# keycontrol1.net
KiCad netlist of a schematic drawn in Altium Designer
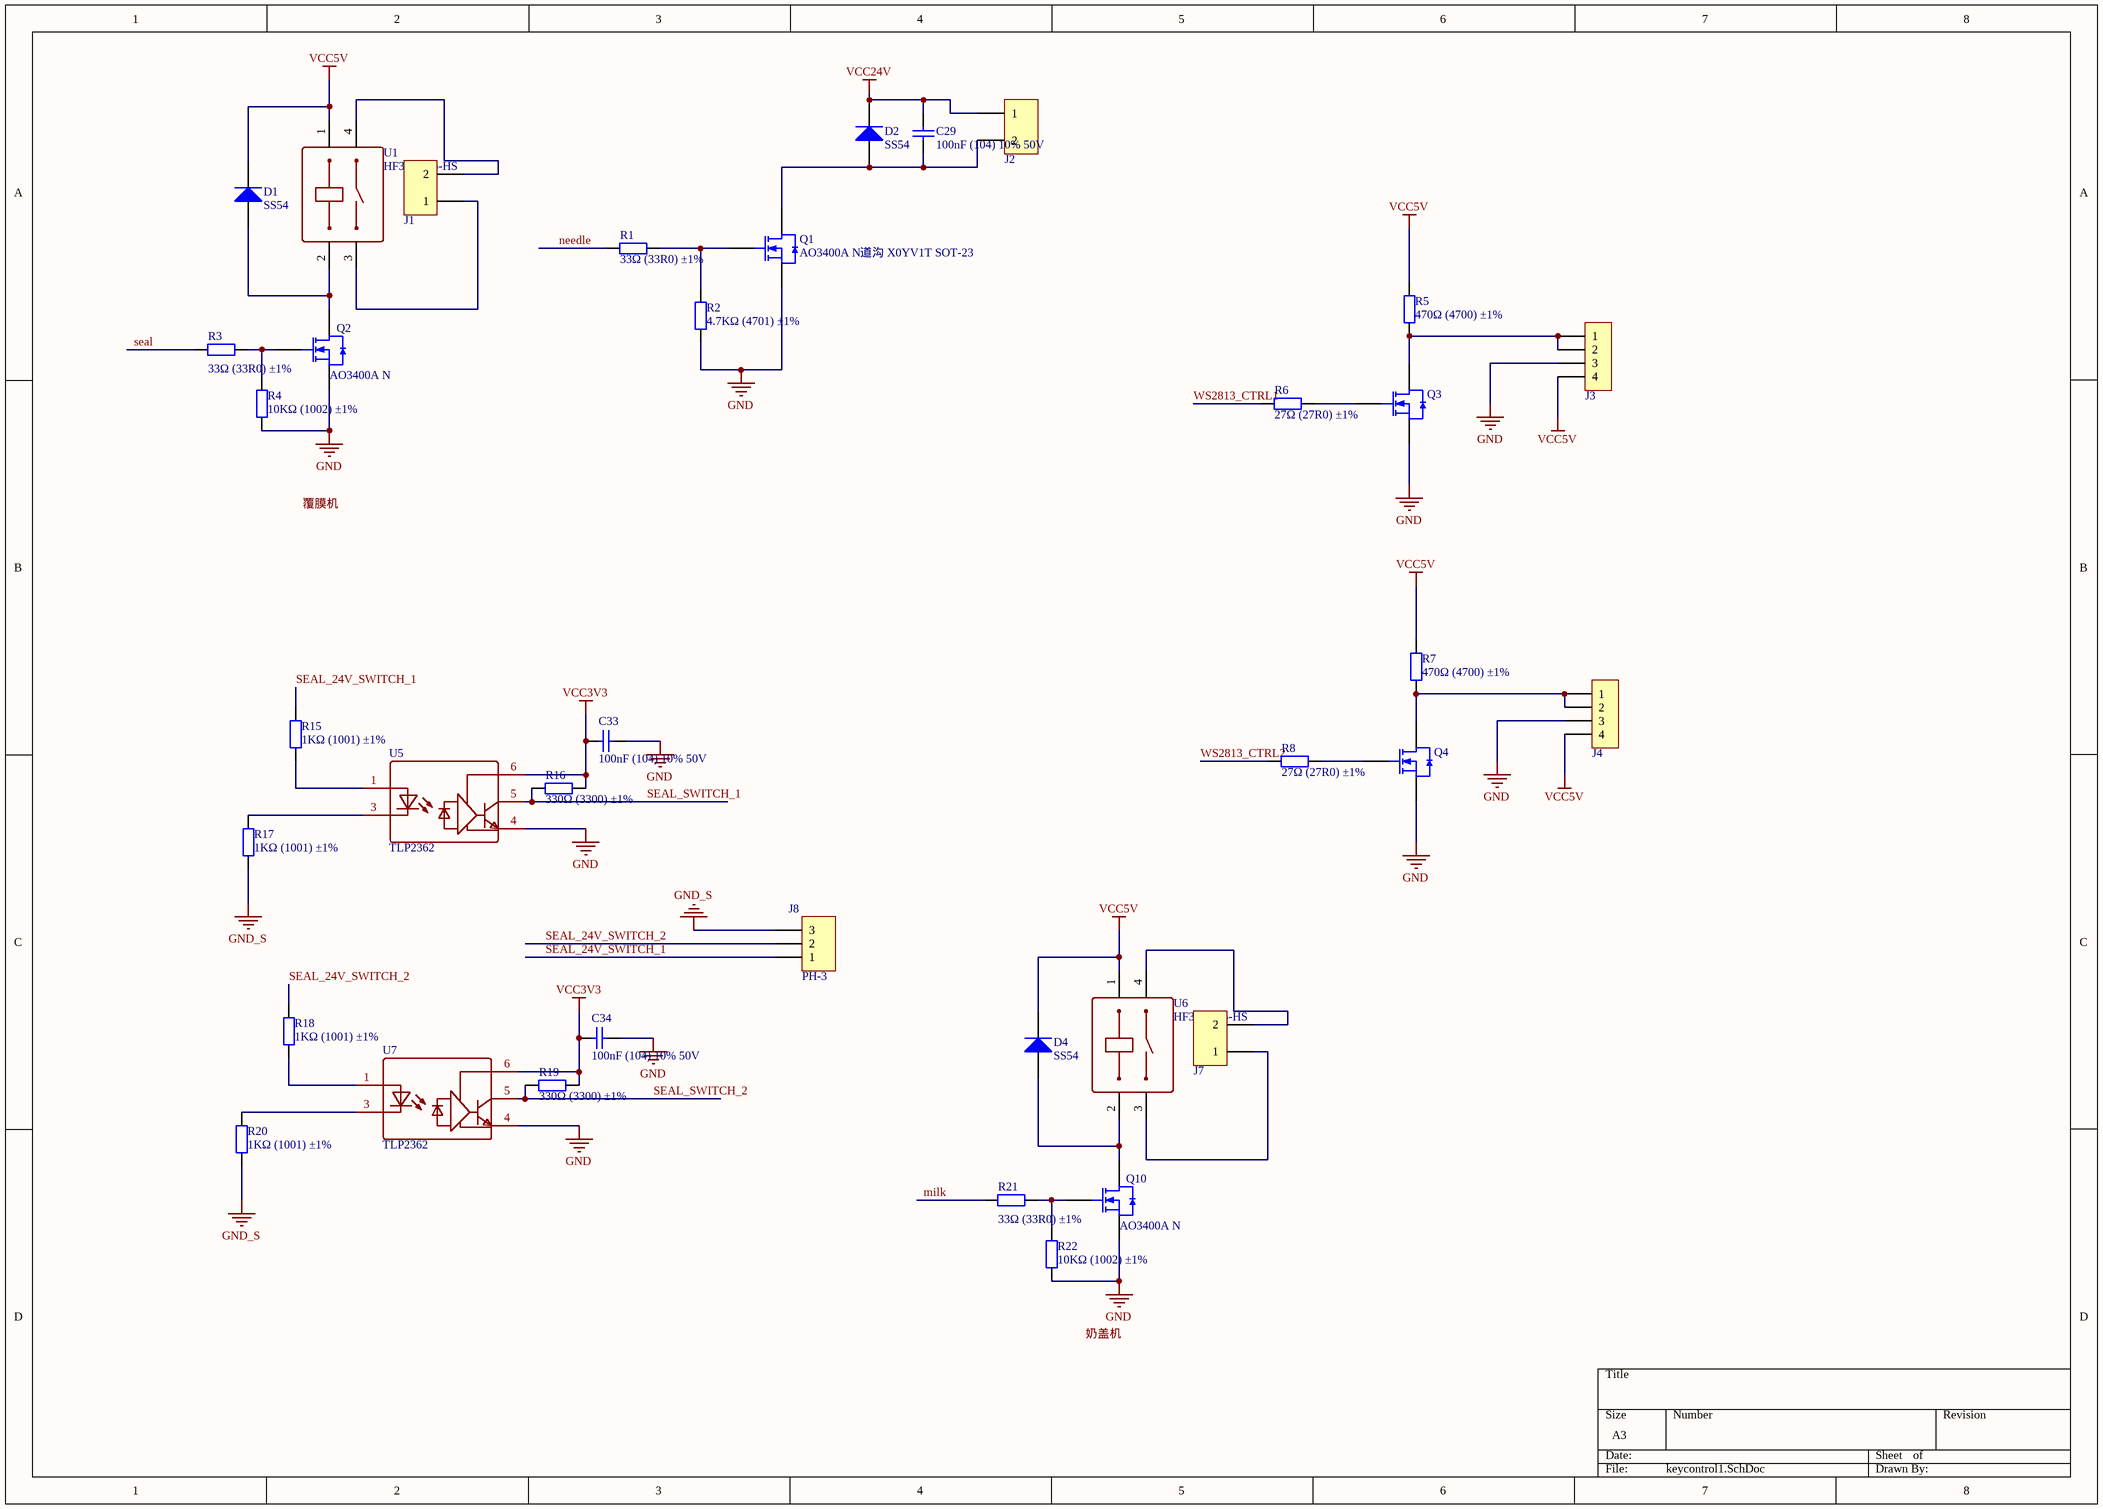
[diagram p0: keycontrol1.SchDoc]

(export (version "E")
  (design (tool "Eeschema 10.0.6"))
  (components
    (comp (ref "C29")
      (value "100nF (104) 10% 50V")
      (footprint "0603_C")
      (description "贴片电容")
      (libsource (lib "AD封装2018.9.19Miscellaneous Devices LC") (part "0603 100nF (104) 10% 50V"))
    )
    (comp (ref "C33")
      (value "100nF (104) 10% 50V")
      (footprint "0603_C")
      (description "贴片电容")
      (libsource (lib "AD封装2018.9.19Miscellaneous Devices LC") (part "0603 100nF (104) 10% 50V"))
    )
    (comp (ref "C34")
      (value "100nF (104) 10% 50V")
      (footprint "0603_C")
      (description "贴片电容")
      (libsource (lib "AD封装2018.9.19Miscellaneous Devices LC") (part "0603 100nF (104) 10% 50V"))
    )
    (comp (ref "D1")
      (value "SS54")
      (footprint "SMA(DO-214AC)_S1")
      (description "二极管")
      (libsource (lib "AD封装2018.9.19Miscellaneous Devices LC") (part "SMA(DO-214AC) SS54"))
    )
    (comp (ref "D2")
      (value "SS54")
      (footprint "SMA(DO-214AC)_S1")
      (description "二极管")
      (libsource (lib "AD封装2018.9.19Miscellaneous Devices LC") (part "SMA(DO-214AC) SS54"))
    )
    (comp (ref "D4")
      (value "SS54")
      (footprint "SMA(DO-214AC)_S1")
      (description "二极管")
      (libsource (lib "AD封装2018.9.19Miscellaneous Devices LC") (part "SMA(DO-214AC) SS54"))
    )
    (comp (ref "J1") (value "MOTOR") (footprint "PH2-2.0") (libsource (lib "我的集成库") (part "header2")))
    (comp (ref "J2") (value "MOTOR") (footprint "XH-2P") (libsource (lib "") (part "header2_1")))
    (comp (ref "J3") (value "header4") (footprint "xh-4") (libsource (lib "我的集成库") (part "header4")))
    (comp (ref "J4") (value "header4") (footprint "xh-4") (libsource (lib "我的集成库") (part "header4")))
    (comp (ref "J7") (value "MOTOR") (footprint "PH2-2.0") (libsource (lib "我的集成库") (part "header2")))
    (comp (ref "J8") (value "PH-3") (footprint "ph3-2.0") (libsource (lib "我的集成库") (part "XH-3")))
    (comp (ref "Q1")
      (value "AO3400A N道沟 X0YV1T SOT-23")
      (footprint "SOT-23-3L")
      (description "MOS(场效应管)")
      (libsource (lib "AD封装2018.9.19Miscellaneous Devices LC") (part "AO3400A N道沟 X0YV1T SOT-23"))
    )
    (comp (ref "Q2")
      (value "AO3400A N")
      (footprint "SOT-23-3L")
      (description "MOS(场效应管)")
      (libsource (lib "AD封装2018.9.19Miscellaneous Devices LC") (part "AO3400A N道沟 X0YV1T SOT-23"))
    )
    (comp (ref "Q3")
      (value "AO3400A N道沟 X0YV1T SOT-23")
      (footprint "SOT-23-3L")
      (description "MOS(场效应管)")
      (libsource (lib "AD封装2018.9.19Miscellaneous Devices LC") (part "AO3400A N道沟 X0YV1T SOT-23"))
    )
    (comp (ref "Q4")
      (value "AO3400A N道沟 X0YV1T SOT-23")
      (footprint "SOT-23-3L")
      (description "MOS(场效应管)")
      (libsource (lib "AD封装2018.9.19Miscellaneous Devices LC") (part "AO3400A N道沟 X0YV1T SOT-23"))
    )
    (comp (ref "Q10")
      (value "AO3400A N")
      (footprint "SOT-23-3L")
      (description "MOS(场效应管)")
      (libsource (lib "AD封装2018.9.19Miscellaneous Devices LC") (part "AO3400A N道沟 X0YV1T SOT-23"))
    )
    (comp (ref "R1")
      (value "33Ω (33R0) ±1%")
      (footprint "0603_R")
      (description "贴片电阻")
      (libsource (lib "AD封装2018.9.19Miscellaneous Devices LC") (part "0603 33Ω (33R0) 1%"))
    )
    (comp (ref "R2")
      (value "4.7KΩ (4701) ±1%")
      (footprint "0603_R")
      (description "贴片电阻")
      (libsource (lib "AD封装2018.9.19Miscellaneous Devices LC") (part "0603 4.7KΩ (4701) 1%"))
    )
    (comp (ref "R3")
      (value "33Ω (33R0) ±1%")
      (footprint "0603_R")
      (description "贴片电阻")
      (libsource (lib "AD封装2018.9.19Miscellaneous Devices LC") (part "0603 33Ω (33R0) 1%"))
    )
    (comp (ref "R4")
      (value "10KΩ (1002) ±1%")
      (footprint "0603_R")
      (description "贴片电阻")
      (libsource (lib "AD封装2018.9.19Miscellaneous Devices LC") (part "0603 10KΩ (1002) 1%"))
    )
    (comp (ref "R5")
      (value "470Ω (4700) ±1%")
      (footprint "0603_R")
      (description "贴片电阻")
      (libsource (lib "AD封装2018.9.19Miscellaneous Devices LC") (part "0603 470Ω (4700) 1%"))
    )
    (comp (ref "R6")
      (value "27Ω (27R0) ±1%")
      (footprint "0603_R")
      (description "贴片电阻")
      (libsource (lib "AD封装2018.9.19Miscellaneous Devices LC") (part "0603 27Ω (27R0) 1%"))
    )
    (comp (ref "R7")
      (value "470Ω (4700) ±1%")
      (footprint "0603_R")
      (description "贴片电阻")
      (libsource (lib "AD封装2018.9.19Miscellaneous Devices LC") (part "0603 470Ω (4700) 1%"))
    )
    (comp (ref "R8")
      (value "27Ω (27R0) ±1%")
      (footprint "0603_R")
      (description "贴片电阻")
      (libsource (lib "AD封装2018.9.19Miscellaneous Devices LC") (part "0603 27Ω (27R0) 1%"))
    )
    (comp (ref "R15")
      (value "1KΩ (1001) ±1%")
      (footprint "1206_R")
      (description "贴片电阻")
      (libsource (lib "AD封装2018.9.19Miscellaneous Devices LC") (part "1206 1KΩ (1001) 1%"))
    )
    (comp (ref "R16")
      (value "330Ω (3300) ±1%")
      (footprint "0603_R")
      (description "贴片电阻")
      (libsource (lib "AD封装2018.9.19Miscellaneous Devices LC") (part "0603 330Ω (3300) 1%"))
    )
    (comp (ref "R17")
      (value "1KΩ (1001) ±1%")
      (footprint "1206_R")
      (description "贴片电阻")
      (libsource (lib "AD封装2018.9.19Miscellaneous Devices LC") (part "1206 1KΩ (1001) 1%"))
    )
    (comp (ref "R18")
      (value "1KΩ (1001) ±1%")
      (footprint "1206_R")
      (description "贴片电阻")
      (libsource (lib "AD封装2018.9.19Miscellaneous Devices LC") (part "1206 1KΩ (1001) 1%"))
    )
    (comp (ref "R19")
      (value "330Ω (3300) ±1%")
      (footprint "0603_R")
      (description "贴片电阻")
      (libsource (lib "AD封装2018.9.19Miscellaneous Devices LC") (part "0603 330Ω (3300) 1%"))
    )
    (comp (ref "R20")
      (value "1KΩ (1001) ±1%")
      (footprint "1206_R")
      (description "贴片电阻")
      (libsource (lib "AD封装2018.9.19Miscellaneous Devices LC") (part "1206 1KΩ (1001) 1%"))
    )
    (comp (ref "R21")
      (value "33Ω (33R0) ±1%")
      (footprint "0603_R")
      (description "贴片电阻")
      (libsource (lib "AD封装2018.9.19Miscellaneous Devices LC") (part "0603 33Ω (33R0) 1%"))
    )
    (comp (ref "R22")
      (value "10KΩ (1002) ±1%")
      (footprint "0603_R")
      (description "贴片电阻")
      (libsource (lib "AD封装2018.9.19Miscellaneous Devices LC") (part "0603 10KΩ (1002) 1%"))
    )
    (comp (ref "U1")
      (value "HF32F/005-HS")
      (footprint "HF32F/005-HS")
      (description "继电器")
      (libsource (lib "我的集成库") (part "HF32F/005-HS"))
    )
    (comp (ref "U5") (value "TLP2362") (footprint "SO-5") (libsource (lib "我的集成库") (part "TLP2362")))
    (comp (ref "U6")
      (value "HF32F/005-HS")
      (footprint "HF32F/005-HS")
      (description "继电器")
      (libsource (lib "我的集成库") (part "HF32F/005-HS"))
    )
    (comp (ref "U7") (value "TLP2362") (footprint "SO-5") (libsource (lib "我的集成库") (part "TLP2362")))
  )
  (nets
    (net (code "1") (name "/SEAL_24V_SWITCH_1") (class "Default")
      (node (ref "J8") (pin "1") (pinfunction "1_1") (pintype "passive"))
      (node (ref "R15") (pin "2") (pinfunction "2_2") (pintype "passive"))
    )
    (net (code "2") (name "/SEAL_24V_SWITCH_2") (class "Default")
      (node (ref "J8") (pin "2") (pinfunction "2_2") (pintype "passive"))
      (node (ref "R18") (pin "2") (pinfunction "2_2") (pintype "passive"))
    )
    (net (code "3") (name "/SEAL_SWITCH_1") (class "Default")
      (node (ref "R16") (pin "1") (pinfunction "1_1") (pintype "passive"))
      (node (ref "U5") (pin "5") (pinfunction "5_5") (pintype "passive"))
    )
    (net (code "4") (name "/SEAL_SWITCH_2") (class "Default")
      (node (ref "R19") (pin "1") (pinfunction "1_1") (pintype "passive"))
      (node (ref "U7") (pin "5") (pinfunction "5_5") (pintype "passive"))
    )
    (net (code "5") (name "/WS2813_CTRL1") (class "Default")
      (node (ref "R6") (pin "1") (pinfunction "1_1") (pintype "passive"))
    )
    (net (code "6") (name "/WS2813_CTRL2") (class "Default")
      (node (ref "R8") (pin "1") (pinfunction "1_1") (pintype "passive"))
    )
    (net (code "7") (name "/milk") (class "Default")
      (node (ref "R21") (pin "1") (pinfunction "1_1") (pintype "passive"))
    )
    (net (code "8") (name "/needle") (class "Default")
      (node (ref "R1") (pin "1") (pinfunction "1_1") (pintype "passive"))
    )
    (net (code "9") (name "/seal") (class "Default")
      (node (ref "R3") (pin "1") (pinfunction "1_1") (pintype "passive"))
    )
    (net (code "12") (name "GND") (class "Default")
      (node (ref "C33") (pin "2") (pinfunction "2_2") (pintype "passive"))
      (node (ref "C34") (pin "2") (pinfunction "2_2") (pintype "passive"))
      (node (ref "J3") (pin "3") (pinfunction "3_3") (pintype "passive"))
      (node (ref "J4") (pin "3") (pinfunction "3_3") (pintype "passive"))
      (node (ref "Q1") (pin "2") (pinfunction "S_2") (pintype "passive"))
      (node (ref "Q10") (pin "2") (pinfunction "S_2") (pintype "passive"))
      (node (ref "Q2") (pin "2") (pinfunction "S_2") (pintype "passive"))
      (node (ref "Q3") (pin "2") (pinfunction "S_2") (pintype "passive"))
      (node (ref "Q4") (pin "2") (pinfunction "S_2") (pintype "passive"))
      (node (ref "R2") (pin "1") (pinfunction "1_1") (pintype "passive"))
      (node (ref "R22") (pin "1") (pinfunction "1_1") (pintype "passive"))
      (node (ref "R4") (pin "1") (pinfunction "1_1") (pintype "passive"))
      (node (ref "U5") (pin "4") (pinfunction "4_4") (pintype "passive"))
      (node (ref "U7") (pin "4") (pinfunction "4_4") (pintype "passive"))
    )
    (net (code "13") (name "GND_S") (class "Default")
      (node (ref "J8") (pin "3") (pinfunction "3_3") (pintype "passive"))
      (node (ref "R17") (pin "1") (pinfunction "1_1") (pintype "passive"))
      (node (ref "R20") (pin "1") (pinfunction "1_1") (pintype "passive"))
    )
    (net (code "14") (name "Net-(D1-A)") (class "Default")
      (node (ref "D1") (pin "1") (pinfunction "A_1") (pintype "passive"))
      (node (ref "Q2") (pin "3") (pinfunction "D_3") (pintype "passive"))
      (node (ref "U1") (pin "2") (pinfunction "2_2") (pintype "passive"))
    )
    (net (code "15") (name "Net-(D2-A)") (class "Default")
      (node (ref "C29") (pin "1") (pinfunction "1_1") (pintype "passive"))
      (node (ref "D2") (pin "1") (pinfunction "A_1") (pintype "passive"))
      (node (ref "J2") (pin "2") (pinfunction "2_2") (pintype "passive"))
      (node (ref "Q1") (pin "3") (pinfunction "D_3") (pintype "passive"))
    )
    (net (code "16") (name "Net-(D4-A)") (class "Default")
      (node (ref "D4") (pin "1") (pinfunction "A_1") (pintype "passive"))
      (node (ref "Q10") (pin "3") (pinfunction "D_3") (pintype "passive"))
      (node (ref "U6") (pin "2") (pinfunction "2_2") (pintype "passive"))
    )
    (net (code "17") (name "Net-(J1-Pad1)") (class "Default")
      (node (ref "J1") (pin "1") (pinfunction "1_1") (pintype "passive"))
      (node (ref "U1") (pin "3") (pinfunction "3_3") (pintype "passive"))
    )
    (net (code "18") (name "Net-(J1-Pad2)") (class "Default")
      (node (ref "J1") (pin "2") (pinfunction "2_2") (pintype "passive"))
      (node (ref "U1") (pin "4") (pinfunction "4_4") (pintype "passive"))
    )
    (net (code "19") (name "Net-(J7-Pad1)") (class "Default")
      (node (ref "J7") (pin "1") (pinfunction "1_1") (pintype "passive"))
      (node (ref "U6") (pin "3") (pinfunction "3_3") (pintype "passive"))
    )
    (net (code "20") (name "Net-(J7-Pad2)") (class "Default")
      (node (ref "J7") (pin "2") (pinfunction "2_2") (pintype "passive"))
      (node (ref "U6") (pin "4") (pinfunction "4_4") (pintype "passive"))
    )
    (net (code "21") (name "Net-(Q1-G)") (class "Default")
      (node (ref "Q1") (pin "1") (pinfunction "G_1") (pintype "passive"))
      (node (ref "R1") (pin "2") (pinfunction "2_2") (pintype "passive"))
      (node (ref "R2") (pin "2") (pinfunction "2_2") (pintype "passive"))
    )
    (net (code "22") (name "Net-(Q2-G)") (class "Default")
      (node (ref "Q2") (pin "1") (pinfunction "G_1") (pintype "passive"))
      (node (ref "R3") (pin "2") (pinfunction "2_2") (pintype "passive"))
      (node (ref "R4") (pin "2") (pinfunction "2_2") (pintype "passive"))
    )
    (net (code "23") (name "Net-(Q3-D)") (class "Default")
      (node (ref "J3") (pin "1") (pinfunction "1_1") (pintype "passive"))
      (node (ref "J3") (pin "2") (pinfunction "2_2") (pintype "passive"))
      (node (ref "Q3") (pin "3") (pinfunction "D_3") (pintype "passive"))
      (node (ref "R5") (pin "1") (pinfunction "1_1") (pintype "passive"))
    )
    (net (code "24") (name "Net-(Q3-G)") (class "Default")
      (node (ref "Q3") (pin "1") (pinfunction "G_1") (pintype "passive"))
      (node (ref "R6") (pin "2") (pinfunction "2_2") (pintype "passive"))
    )
    (net (code "25") (name "Net-(Q4-D)") (class "Default")
      (node (ref "J4") (pin "1") (pinfunction "1_1") (pintype "passive"))
      (node (ref "J4") (pin "2") (pinfunction "2_2") (pintype "passive"))
      (node (ref "Q4") (pin "3") (pinfunction "D_3") (pintype "passive"))
      (node (ref "R7") (pin "1") (pinfunction "1_1") (pintype "passive"))
    )
    (net (code "26") (name "Net-(Q4-G)") (class "Default")
      (node (ref "Q4") (pin "1") (pinfunction "G_1") (pintype "passive"))
      (node (ref "R8") (pin "2") (pinfunction "2_2") (pintype "passive"))
    )
    (net (code "27") (name "Net-(Q10-G)") (class "Default")
      (node (ref "Q10") (pin "1") (pinfunction "G_1") (pintype "passive"))
      (node (ref "R21") (pin "2") (pinfunction "2_2") (pintype "passive"))
      (node (ref "R22") (pin "2") (pinfunction "2_2") (pintype "passive"))
    )
    (net (code "28") (name "Net-(R15-Pad1)") (class "Default")
      (node (ref "R15") (pin "1") (pinfunction "1_1") (pintype "passive"))
      (node (ref "U5") (pin "1") (pinfunction "1_1") (pintype "passive"))
    )
    (net (code "29") (name "Net-(R17-Pad2)") (class "Default")
      (node (ref "R17") (pin "2") (pinfunction "2_2") (pintype "passive"))
      (node (ref "U5") (pin "3") (pinfunction "3_3") (pintype "passive"))
    )
    (net (code "30") (name "Net-(R18-Pad1)") (class "Default")
      (node (ref "R18") (pin "1") (pinfunction "1_1") (pintype "passive"))
      (node (ref "U7") (pin "1") (pinfunction "1_1") (pintype "passive"))
    )
    (net (code "31") (name "Net-(R20-Pad2)") (class "Default")
      (node (ref "R20") (pin "2") (pinfunction "2_2") (pintype "passive"))
      (node (ref "U7") (pin "3") (pinfunction "3_3") (pintype "passive"))
    )
    (net (code "32") (name "VCC3V3") (class "Default")
      (node (ref "C33") (pin "1") (pinfunction "1_1") (pintype "passive"))
      (node (ref "C34") (pin "1") (pinfunction "1_1") (pintype "passive"))
      (node (ref "R16") (pin "2") (pinfunction "2_2") (pintype "passive"))
      (node (ref "R19") (pin "2") (pinfunction "2_2") (pintype "passive"))
      (node (ref "U5") (pin "6") (pinfunction "6_6") (pintype "passive"))
      (node (ref "U7") (pin "6") (pinfunction "6_6") (pintype "passive"))
    )
    (net (code "33") (name "VCC5V") (class "Default")
      (node (ref "D1") (pin "2") (pinfunction "K_2") (pintype "passive"))
      (node (ref "D4") (pin "2") (pinfunction "K_2") (pintype "passive"))
      (node (ref "J3") (pin "4") (pinfunction "4_4") (pintype "passive"))
      (node (ref "J4") (pin "4") (pinfunction "4_4") (pintype "passive"))
      (node (ref "R5") (pin "2") (pinfunction "2_2") (pintype "passive"))
      (node (ref "R7") (pin "2") (pinfunction "2_2") (pintype "passive"))
      (node (ref "U1") (pin "1") (pinfunction "1_1") (pintype "passive"))
      (node (ref "U6") (pin "1") (pinfunction "1_1") (pintype "passive"))
    )
    (net (code "34") (name "VCC24V") (class "Default")
      (node (ref "C29") (pin "2") (pinfunction "2_2") (pintype "passive"))
      (node (ref "D2") (pin "2") (pinfunction "K_2") (pintype "passive"))
      (node (ref "J2") (pin "1") (pinfunction "1_1") (pintype "passive"))
    )
  )
)
